# 4_waffling60-NMB_periferals.net
KiCad netlist of a schematic drawn in Altium Designer
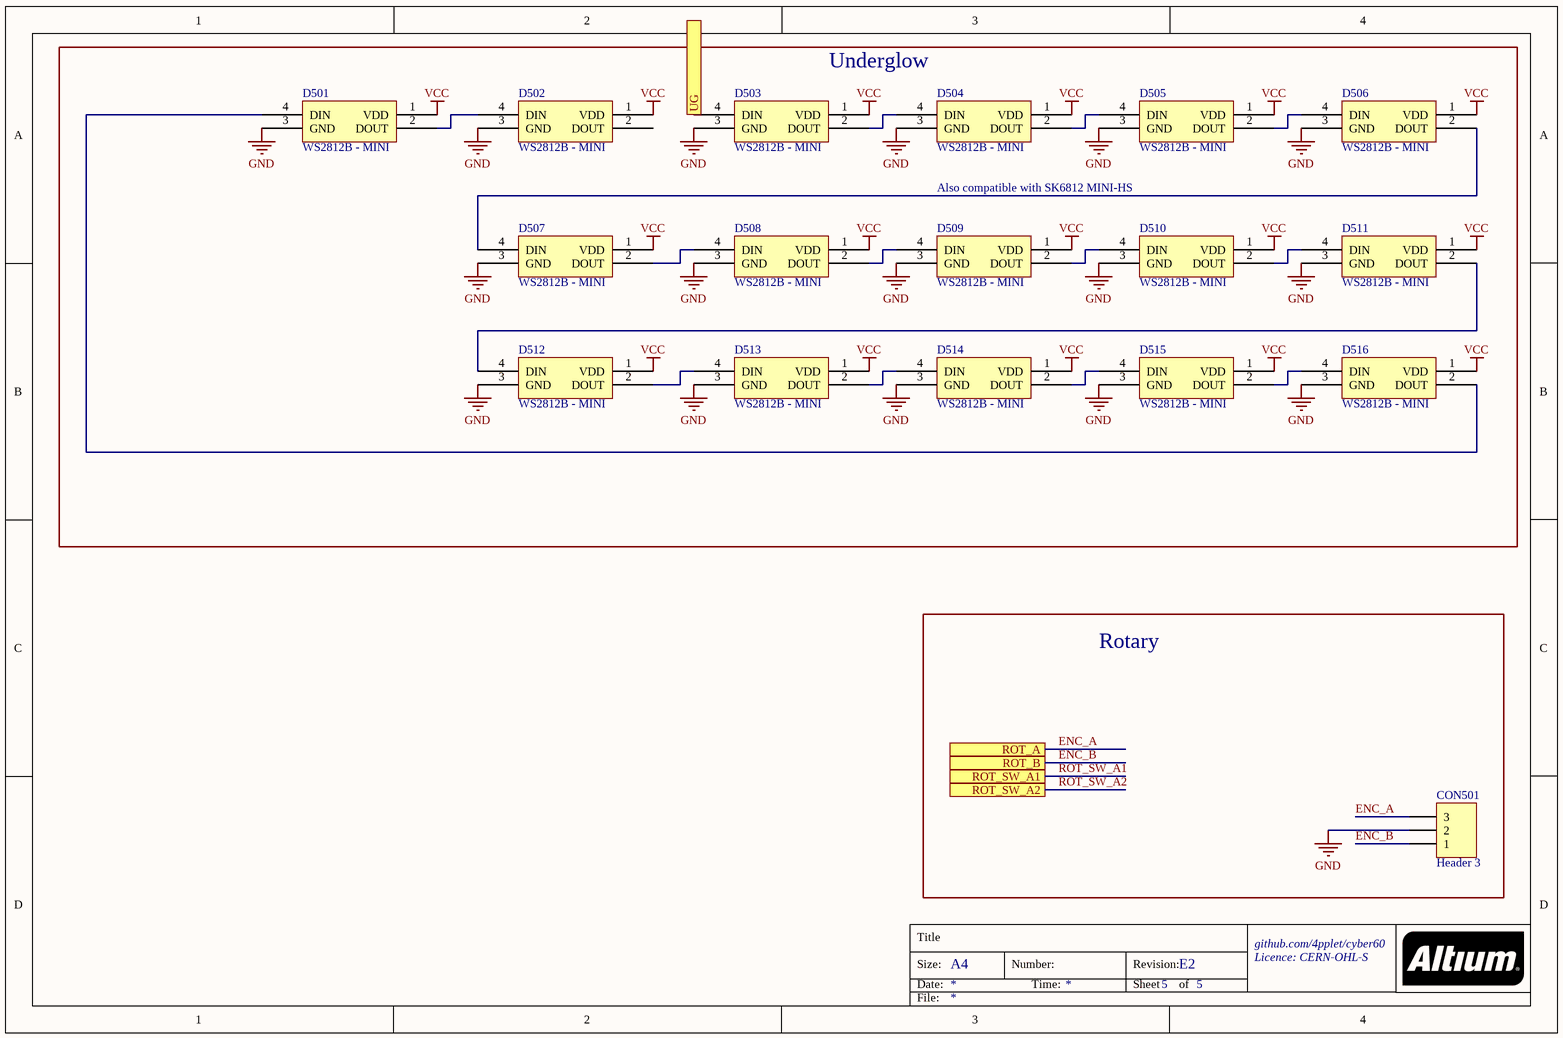
[diagram p0: 4_waffling60-NMB_periferals.SchDoc]

(export (version "E")
  (design (tool "Eeschema 10.0.6"))
  (components
    (comp (ref "CON501")
      (value "Header 3")
      (footprint "HDR1X3")
      (description "Header, 3-Pin")
      (libsource (lib "Miscellaneous Connectors") (part "Header 3"))
    )
    (comp (ref "D501")
      (value "WS2812B - MINI")
      (footprint "WS2812B - 2020")
      (fields (field (name "LCSC PART #") "C965555") (field (name "MRF.PART") "WS2812B-2020"))
      (libsource (lib "Keebs") (part "WS2812B"))
    )
    (comp (ref "D502")
      (value "WS2812B - MINI")
      (footprint "WS2812B - 2020")
      (fields (field (name "LCSC PART #") "C965555") (field (name "MRF.PART") "WS2812B-2020"))
      (libsource (lib "Keebs") (part "WS2812B"))
    )
    (comp (ref "D503")
      (value "WS2812B - MINI")
      (footprint "WS2812B - 2020")
      (fields (field (name "LCSC PART #") "C965555") (field (name "MRF.PART") "WS2812B-2020"))
      (libsource (lib "Keebs") (part "WS2812B"))
    )
    (comp (ref "D504")
      (value "WS2812B - MINI")
      (footprint "WS2812B - 2020")
      (fields (field (name "LCSC PART #") "C965555") (field (name "MRF.PART") "WS2812B-2020"))
      (libsource (lib "Keebs") (part "WS2812B"))
    )
    (comp (ref "D505")
      (value "WS2812B - MINI")
      (footprint "WS2812B - 2020")
      (fields (field (name "LCSC PART #") "C965555") (field (name "MRF.PART") "WS2812B-2020"))
      (libsource (lib "Keebs") (part "WS2812B"))
    )
    (comp (ref "D506")
      (value "WS2812B - MINI")
      (footprint "WS2812B - 2020")
      (fields (field (name "LCSC PART #") "C965555") (field (name "MRF.PART") "WS2812B-2020"))
      (libsource (lib "Keebs") (part "WS2812B"))
    )
    (comp (ref "D507")
      (value "WS2812B - MINI")
      (footprint "WS2812B - 2020")
      (fields (field (name "LCSC PART #") "C965555") (field (name "MRF.PART") "WS2812B-2020"))
      (libsource (lib "Keebs") (part "WS2812B"))
    )
    (comp (ref "D508")
      (value "WS2812B - MINI")
      (footprint "WS2812B - 2020")
      (fields (field (name "LCSC PART #") "C965555") (field (name "MRF.PART") "WS2812B-2020"))
      (libsource (lib "Keebs") (part "WS2812B"))
    )
    (comp (ref "D509")
      (value "WS2812B - MINI")
      (footprint "WS2812B - 2020")
      (fields (field (name "LCSC PART #") "C965555") (field (name "MRF.PART") "WS2812B-2020"))
      (libsource (lib "Keebs") (part "WS2812B"))
    )
    (comp (ref "D510")
      (value "WS2812B - MINI")
      (footprint "WS2812B - 2020")
      (fields (field (name "LCSC PART #") "C965555") (field (name "MRF.PART") "WS2812B-2020"))
      (libsource (lib "Keebs") (part "WS2812B"))
    )
    (comp (ref "D511")
      (value "WS2812B - MINI")
      (footprint "WS2812B - 2020")
      (fields (field (name "LCSC PART #") "C965555") (field (name "MRF.PART") "WS2812B-2020"))
      (libsource (lib "Keebs") (part "WS2812B"))
    )
    (comp (ref "D512")
      (value "WS2812B - MINI")
      (footprint "WS2812B - 2020")
      (fields (field (name "LCSC PART #") "C965555") (field (name "MRF.PART") "WS2812B-2020"))
      (libsource (lib "Keebs") (part "WS2812B"))
    )
    (comp (ref "D513")
      (value "WS2812B - MINI")
      (footprint "WS2812B - 2020")
      (fields (field (name "LCSC PART #") "C965555") (field (name "MRF.PART") "WS2812B-2020"))
      (libsource (lib "Keebs") (part "WS2812B"))
    )
    (comp (ref "D514")
      (value "WS2812B - MINI")
      (footprint "WS2812B - 2020")
      (fields (field (name "LCSC PART #") "C965555") (field (name "MRF.PART") "WS2812B-2020"))
      (libsource (lib "Keebs") (part "WS2812B"))
    )
    (comp (ref "D515")
      (value "WS2812B - MINI")
      (footprint "WS2812B - 2020")
      (fields (field (name "LCSC PART #") "C965555") (field (name "MRF.PART") "WS2812B-2020"))
      (libsource (lib "Keebs") (part "WS2812B"))
    )
    (comp (ref "D516")
      (value "WS2812B - MINI")
      (footprint "WS2812B - 2020")
      (fields (field (name "LCSC PART #") "C965555") (field (name "MRF.PART") "WS2812B-2020"))
      (libsource (lib "Keebs") (part "WS2812B"))
    )
  )
  (nets
    (net (code "1") (name "/ENC_A") (class "Default")
      (node (ref "CON501") (pin "3") (pinfunction "3_3") (pintype "passive"))
    )
    (net (code "2") (name "/ENC_B") (class "Default")
      (node (ref "CON501") (pin "1") (pinfunction "1_1") (pintype "passive"))
    )
    (net (code "5") (name "/UG") (class "Default")
      (node (ref "D503") (pin "4") (pinfunction "DIN_4") (pintype "passive"))
    )
    (net (code "6") (name "GND") (class "Default")
      (node (ref "CON501") (pin "2") (pinfunction "2_2") (pintype "passive"))
      (node (ref "D501") (pin "3") (pinfunction "GND_3") (pintype "passive"))
      (node (ref "D502") (pin "3") (pinfunction "GND_3") (pintype "passive"))
      (node (ref "D503") (pin "3") (pinfunction "GND_3") (pintype "passive"))
      (node (ref "D504") (pin "3") (pinfunction "GND_3") (pintype "passive"))
      (node (ref "D505") (pin "3") (pinfunction "GND_3") (pintype "passive"))
      (node (ref "D506") (pin "3") (pinfunction "GND_3") (pintype "passive"))
      (node (ref "D507") (pin "3") (pinfunction "GND_3") (pintype "passive"))
      (node (ref "D508") (pin "3") (pinfunction "GND_3") (pintype "passive"))
      (node (ref "D509") (pin "3") (pinfunction "GND_3") (pintype "passive"))
      (node (ref "D510") (pin "3") (pinfunction "GND_3") (pintype "passive"))
      (node (ref "D511") (pin "3") (pinfunction "GND_3") (pintype "passive"))
      (node (ref "D512") (pin "3") (pinfunction "GND_3") (pintype "passive"))
      (node (ref "D513") (pin "3") (pinfunction "GND_3") (pintype "passive"))
      (node (ref "D514") (pin "3") (pinfunction "GND_3") (pintype "passive"))
      (node (ref "D515") (pin "3") (pinfunction "GND_3") (pintype "passive"))
      (node (ref "D516") (pin "3") (pinfunction "GND_3") (pintype "passive"))
    )
    (net (code "7") (name "Net-(D501-DIN)") (class "Default")
      (node (ref "D501") (pin "4") (pinfunction "DIN_4") (pintype "passive"))
      (node (ref "D516") (pin "2") (pinfunction "DOUT_2") (pintype "passive"))
    )
    (net (code "8") (name "Net-(D501-DOUT)") (class "Default")
      (node (ref "D501") (pin "2") (pinfunction "DOUT_2") (pintype "passive"))
      (node (ref "D502") (pin "4") (pinfunction "DIN_4") (pintype "passive"))
    )
    (net (code "9") (name "Net-(D503-DOUT)") (class "Default")
      (node (ref "D503") (pin "2") (pinfunction "DOUT_2") (pintype "passive"))
      (node (ref "D504") (pin "4") (pinfunction "DIN_4") (pintype "passive"))
    )
    (net (code "10") (name "Net-(D504-DOUT)") (class "Default")
      (node (ref "D504") (pin "2") (pinfunction "DOUT_2") (pintype "passive"))
      (node (ref "D505") (pin "4") (pinfunction "DIN_4") (pintype "passive"))
    )
    (net (code "11") (name "Net-(D505-DOUT)") (class "Default")
      (node (ref "D505") (pin "2") (pinfunction "DOUT_2") (pintype "passive"))
      (node (ref "D506") (pin "4") (pinfunction "DIN_4") (pintype "passive"))
    )
    (net (code "12") (name "Net-(D506-DOUT)") (class "Default")
      (node (ref "D506") (pin "2") (pinfunction "DOUT_2") (pintype "passive"))
      (node (ref "D507") (pin "4") (pinfunction "DIN_4") (pintype "passive"))
    )
    (net (code "13") (name "Net-(D507-DOUT)") (class "Default")
      (node (ref "D507") (pin "2") (pinfunction "DOUT_2") (pintype "passive"))
      (node (ref "D508") (pin "4") (pinfunction "DIN_4") (pintype "passive"))
    )
    (net (code "14") (name "Net-(D508-DOUT)") (class "Default")
      (node (ref "D508") (pin "2") (pinfunction "DOUT_2") (pintype "passive"))
      (node (ref "D509") (pin "4") (pinfunction "DIN_4") (pintype "passive"))
    )
    (net (code "15") (name "Net-(D509-DOUT)") (class "Default")
      (node (ref "D509") (pin "2") (pinfunction "DOUT_2") (pintype "passive"))
      (node (ref "D510") (pin "4") (pinfunction "DIN_4") (pintype "passive"))
    )
    (net (code "16") (name "Net-(D510-DOUT)") (class "Default")
      (node (ref "D510") (pin "2") (pinfunction "DOUT_2") (pintype "passive"))
      (node (ref "D511") (pin "4") (pinfunction "DIN_4") (pintype "passive"))
    )
    (net (code "17") (name "Net-(D511-DOUT)") (class "Default")
      (node (ref "D511") (pin "2") (pinfunction "DOUT_2") (pintype "passive"))
      (node (ref "D512") (pin "4") (pinfunction "DIN_4") (pintype "passive"))
    )
    (net (code "18") (name "Net-(D512-DOUT)") (class "Default")
      (node (ref "D512") (pin "2") (pinfunction "DOUT_2") (pintype "passive"))
      (node (ref "D513") (pin "4") (pinfunction "DIN_4") (pintype "passive"))
    )
    (net (code "19") (name "Net-(D513-DOUT)") (class "Default")
      (node (ref "D513") (pin "2") (pinfunction "DOUT_2") (pintype "passive"))
      (node (ref "D514") (pin "4") (pinfunction "DIN_4") (pintype "passive"))
    )
    (net (code "20") (name "Net-(D514-DOUT)") (class "Default")
      (node (ref "D514") (pin "2") (pinfunction "DOUT_2") (pintype "passive"))
      (node (ref "D515") (pin "4") (pinfunction "DIN_4") (pintype "passive"))
    )
    (net (code "21") (name "Net-(D515-DOUT)") (class "Default")
      (node (ref "D515") (pin "2") (pinfunction "DOUT_2") (pintype "passive"))
      (node (ref "D516") (pin "4") (pinfunction "DIN_4") (pintype "passive"))
    )
    (net (code "22") (name "VCC") (class "Default")
      (node (ref "D501") (pin "1") (pinfunction "VDD_1") (pintype "passive"))
      (node (ref "D502") (pin "1") (pinfunction "VDD_1") (pintype "passive"))
      (node (ref "D503") (pin "1") (pinfunction "VDD_1") (pintype "passive"))
      (node (ref "D504") (pin "1") (pinfunction "VDD_1") (pintype "passive"))
      (node (ref "D505") (pin "1") (pinfunction "VDD_1") (pintype "passive"))
      (node (ref "D506") (pin "1") (pinfunction "VDD_1") (pintype "passive"))
      (node (ref "D507") (pin "1") (pinfunction "VDD_1") (pintype "passive"))
      (node (ref "D508") (pin "1") (pinfunction "VDD_1") (pintype "passive"))
      (node (ref "D509") (pin "1") (pinfunction "VDD_1") (pintype "passive"))
      (node (ref "D510") (pin "1") (pinfunction "VDD_1") (pintype "passive"))
      (node (ref "D511") (pin "1") (pinfunction "VDD_1") (pintype "passive"))
      (node (ref "D512") (pin "1") (pinfunction "VDD_1") (pintype "passive"))
      (node (ref "D513") (pin "1") (pinfunction "VDD_1") (pintype "passive"))
      (node (ref "D514") (pin "1") (pinfunction "VDD_1") (pintype "passive"))
      (node (ref "D515") (pin "1") (pinfunction "VDD_1") (pintype "passive"))
      (node (ref "D516") (pin "1") (pinfunction "VDD_1") (pintype "passive"))
    )
    (net (code "23") (name "unconnected-(D502-DOUT-Pad2)") (class "Default")
      (node (ref "D502") (pin "2") (pinfunction "DOUT_2") (pintype "passive"))
    )
  )
)
